# Power_output.net
KiCad netlist of a schematic drawn in Altium Designer
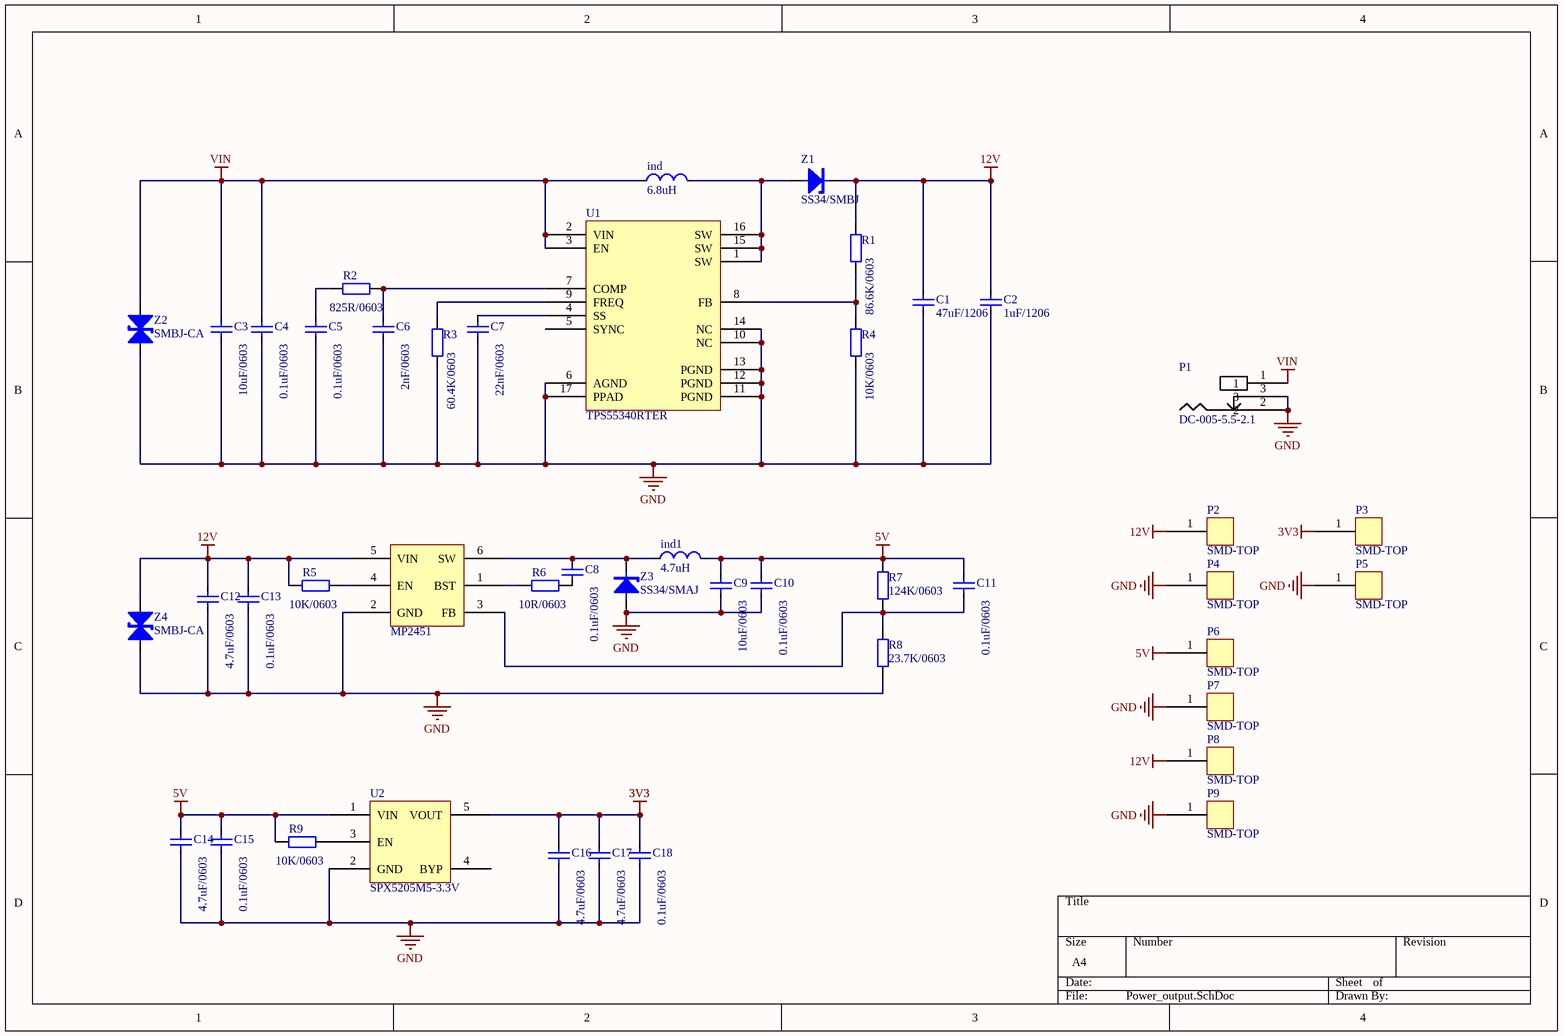
[diagram p0: Power_output.SchDoc]

(export (version "E")
  (design (tool "Eeschema 10.0.6"))
  (components
    (comp (ref "C1")
      (value "47uF/1206")
      (footprint "CAP_1206")
      (description "Capacitor")
      (fields (field (name "Comment") "?uF"))
      (libsource (lib "SchLibrary ") (part "Cap_1206"))
    )
    (comp (ref "C2")
      (value "1uF/1206")
      (footprint "CAP_1206")
      (description "Capacitor")
      (fields (field (name "Comment") "?uF"))
      (libsource (lib "SchLibrary ") (part "Cap_1206"))
    )
    (comp (ref "C3")
      (value "10uF/0603")
      (footprint "CAP_0603")
      (description "Capacitor")
      (fields (field (name "Comment") "?uF"))
      (libsource (lib "SchLibrary ") (part "Cap_0603"))
    )
    (comp (ref "C4")
      (value "0.1uF/0603")
      (footprint "CAP_0603")
      (description "Capacitor")
      (fields (field (name "Comment") "?uF"))
      (libsource (lib "SchLibrary ") (part "Cap_0603"))
    )
    (comp (ref "C5")
      (value "0.1uF/0603")
      (footprint "CAP_0603")
      (description "Capacitor")
      (fields (field (name "Comment") "?uF"))
      (libsource (lib "SchLibrary ") (part "Cap_0603"))
    )
    (comp (ref "C6")
      (value "2nF/0603")
      (footprint "CAP_0603")
      (description "Capacitor")
      (fields (field (name "Comment") "?uF"))
      (libsource (lib "SchLibrary ") (part "Cap_0603"))
    )
    (comp (ref "C7")
      (value "22nF/0603")
      (footprint "CAP_0603")
      (description "Capacitor")
      (fields (field (name "Comment") "?uF"))
      (libsource (lib "SchLibrary ") (part "Cap_0603"))
    )
    (comp (ref "C8")
      (value "0.1uF/0603")
      (footprint "CAP_0603")
      (description "Capacitor")
      (fields (field (name "Comment") "?uF"))
      (libsource (lib "SchLibrary ") (part "Cap_0603"))
    )
    (comp (ref "C9")
      (value "10uF/0603")
      (footprint "CAP_0603")
      (description "Capacitor")
      (fields (field (name "Comment") "?uF"))
      (libsource (lib "SchLibrary ") (part "Cap_0603"))
    )
    (comp (ref "C10")
      (value "0.1uF/0603")
      (footprint "CAP_0603")
      (description "Capacitor")
      (fields (field (name "Comment") "?uF"))
      (libsource (lib "SchLibrary ") (part "Cap_0603"))
    )
    (comp (ref "C11")
      (value "0.1uF/0603")
      (footprint "CAP_0603")
      (description "Capacitor")
      (fields (field (name "Comment") "?uF"))
      (libsource (lib "SchLibrary ") (part "Cap_0603"))
    )
    (comp (ref "C12")
      (value "4.7uF/0603")
      (footprint "CAP_0603")
      (description "Capacitor")
      (fields (field (name "Comment") "?uF"))
      (libsource (lib "SchLibrary ") (part "Cap_0603"))
    )
    (comp (ref "C13")
      (value "0.1uF/0603")
      (footprint "CAP_0603")
      (description "Capacitor")
      (fields (field (name "Comment") "?uF"))
      (libsource (lib "SchLibrary ") (part "Cap_0603"))
    )
    (comp (ref "C14")
      (value "4.7uF/0603")
      (footprint "CAP_0603")
      (description "Capacitor")
      (fields (field (name "Comment") "?uF"))
      (libsource (lib "SchLibrary ") (part "Cap_0603"))
    )
    (comp (ref "C15")
      (value "0.1uF/0603")
      (footprint "CAP_0603")
      (description "Capacitor")
      (fields (field (name "Comment") "?uF"))
      (libsource (lib "SchLibrary ") (part "Cap_0603"))
    )
    (comp (ref "C16")
      (value "4.7uF/0603")
      (footprint "CAP_0603")
      (description "Capacitor")
      (fields (field (name "Comment") "?uF"))
      (libsource (lib "SchLibrary ") (part "Cap_0603"))
    )
    (comp (ref "C17")
      (value "4.7uF/0603")
      (footprint "CAP_0603")
      (description "Capacitor")
      (fields (field (name "Comment") "?uF"))
      (libsource (lib "SchLibrary ") (part "Cap_0603"))
    )
    (comp (ref "C18")
      (value "0.1uF/0603")
      (footprint "CAP_0603")
      (description "Capacitor")
      (fields (field (name "Comment") "?uF"))
      (libsource (lib "SchLibrary ") (part "Cap_0603"))
    )
    (comp (ref "ind") (value "6.8uH") (footprint "IND4*4*2") (libsource (lib "SchLibrary ") (part "Ind")))
    (comp (ref "ind1") (value "4.7uH") (footprint "IND4*4*2") (libsource (lib "SchLibrary ") (part "Ind")))
    (comp (ref "MP2451")
      (value "MP2451")
      (footprint "SOT23-6")
      (description "降压转换器")
      (libsource (lib "SchLibrary ") (part "MP2451"))
    )
    (comp (ref "P1")
      (value "DC-005-5.5-2.1")
      (footprint "DC-005")
      (libsource (lib "SchLibrary ") (part "DC-005-5.5-2.1"))
    )
    (comp (ref "P2") (value "SMD-TOP") (footprint "SMD-TOP") (libsource (lib "SchLibrary ") (part "SMD-TOP")))
    (comp (ref "P3") (value "SMD-TOP") (footprint "SMD-TOP") (libsource (lib "SchLibrary ") (part "SMD-TOP")))
    (comp (ref "P4") (value "SMD-TOP") (footprint "SMD-TOP") (libsource (lib "SchLibrary ") (part "SMD-TOP")))
    (comp (ref "P5") (value "SMD-TOP") (footprint "SMD-TOP") (libsource (lib "SchLibrary ") (part "SMD-TOP")))
    (comp (ref "P6") (value "SMD-TOP") (footprint "SMD-TOP") (libsource (lib "SchLibrary ") (part "SMD-TOP")))
    (comp (ref "P7") (value "SMD-TOP") (footprint "SMD-TOP") (libsource (lib "SchLibrary ") (part "SMD-TOP")))
    (comp (ref "P8") (value "SMD-TOP") (footprint "SMD-TOP") (libsource (lib "SchLibrary ") (part "SMD-TOP")))
    (comp (ref "P9") (value "SMD-TOP") (footprint "SMD-TOP") (libsource (lib "SchLibrary ") (part "SMD-TOP")))
    (comp (ref "R1")
      (value "86.6K/0603")
      (footprint "RES_0603")
      (description "Resistor")
      (fields (field (name "Comment") "?K"))
      (libsource (lib "SchLibrary ") (part "Res_0603"))
    )
    (comp (ref "R2")
      (value "825R/0603")
      (footprint "RES_0603")
      (description "Resistor")
      (fields (field (name "Comment") "?K"))
      (libsource (lib "") (part "Res_0603_1"))
    )
    (comp (ref "R3")
      (value "60.4K/0603")
      (footprint "RES_0603")
      (description "Resistor")
      (fields (field (name "Comment") "?K"))
      (libsource (lib "SchLibrary ") (part "Res_0603"))
    )
    (comp (ref "R4")
      (value "10K/0603")
      (footprint "RES_0603")
      (description "Resistor")
      (fields (field (name "Comment") "?K"))
      (libsource (lib "SchLibrary ") (part "Res_0603"))
    )
    (comp (ref "R5")
      (value "10K/0603")
      (footprint "RES_0603")
      (description "Resistor")
      (fields (field (name "Comment") "?K"))
      (libsource (lib "") (part "Res_0603_1"))
    )
    (comp (ref "R6")
      (value "10R/0603")
      (footprint "RES_0603")
      (description "Resistor")
      (fields (field (name "Comment") "?K"))
      (libsource (lib "") (part "Res_0603_1"))
    )
    (comp (ref "R7")
      (value "124K/0603")
      (footprint "RES_0603")
      (description "Resistor")
      (fields (field (name "Comment") "?K"))
      (libsource (lib "SchLibrary ") (part "Res_0603"))
    )
    (comp (ref "R8")
      (value "23.7K/0603")
      (footprint "RES_0603")
      (description "Resistor")
      (fields (field (name "Comment") "?K"))
      (libsource (lib "SchLibrary ") (part "Res_0603"))
    )
    (comp (ref "R9")
      (value "10K/0603")
      (footprint "RES_0603")
      (description "Resistor")
      (fields (field (name "Comment") "?K"))
      (libsource (lib "") (part "Res_0603_1"))
    )
    (comp (ref "U1")
      (value "TPS55340RTER")
      (footprint "WQFN16")
      (libsource (lib "SchLibrary ") (part "TPS55340RTER"))
    )
    (comp (ref "U2")
      (value "SPX5205M5-3.3V")
      (footprint "SOT23-5")
      (description "LDO IC")
      (libsource (lib "SchLibrary ") (part "SPX5205M5-3.3V"))
    )
    (comp (ref "Z1")
      (value "SS34/SMBJ")
      (footprint "SMB")
      (description "TVS")
      (libsource (lib "SchLibrary ") (part "SMBJ"))
    )
    (comp (ref "Z2")
      (value "SMBJ-CA")
      (footprint "SMB( No proporcionado)")
      (description "TVS")
      (libsource (lib "SchLibrary ") (part "SMBJ-CA"))
    )
    (comp (ref "Z3")
      (value "SS34/SMAJ")
      (footprint "SMA")
      (description "TVS")
      (libsource (lib "SchLibrary ") (part "SMAJ"))
    )
    (comp (ref "Z4")
      (value "SMBJ-CA")
      (footprint "SMB( No proporcionado)")
      (description "TVS")
      (libsource (lib "SchLibrary ") (part "SMBJ-CA"))
    )
  )
  (nets
    (net (code "1") (name "3V3") (class "Default")
      (node (ref "C16") (pin "2") (pinfunction "2_2") (pintype "passive"))
      (node (ref "C17") (pin "2") (pinfunction "2_2") (pintype "passive"))
      (node (ref "C18") (pin "2") (pinfunction "2_2") (pintype "passive"))
      (node (ref "P3") (pin "1") (pinfunction "1_1") (pintype "passive"))
      (node (ref "U2") (pin "5") (pinfunction "VOUT_5") (pintype "passive"))
    )
    (net (code "2") (name "5V") (class "Default")
      (node (ref "C10") (pin "2") (pinfunction "2_2") (pintype "passive"))
      (node (ref "C11") (pin "2") (pinfunction "2_2") (pintype "passive"))
      (node (ref "C14") (pin "2") (pinfunction "2_2") (pintype "passive"))
      (node (ref "C15") (pin "2") (pinfunction "2_2") (pintype "passive"))
      (node (ref "C9") (pin "2") (pinfunction "2_2") (pintype "passive"))
      (node (ref "P6") (pin "1") (pinfunction "1_1") (pintype "passive"))
      (node (ref "R7") (pin "2") (pinfunction "2_2") (pintype "passive"))
      (node (ref "R9") (pin "1") (pinfunction "1_1") (pintype "passive"))
      (node (ref "U2") (pin "1") (pinfunction "VIN_1") (pintype "passive"))
      (node (ref "ind1") (pin "2") (pinfunction "2_2") (pintype "passive"))
    )
    (net (code "3") (name "12V") (class "Default")
      (node (ref "C1") (pin "2") (pinfunction "2_2") (pintype "passive"))
      (node (ref "C12") (pin "2") (pinfunction "2_2") (pintype "passive"))
      (node (ref "C13") (pin "2") (pinfunction "2_2") (pintype "passive"))
      (node (ref "C2") (pin "2") (pinfunction "2_2") (pintype "passive"))
      (node (ref "MP2451") (pin "5") (pinfunction "VIN_5") (pintype "passive"))
      (node (ref "P2") (pin "1") (pinfunction "1_1") (pintype "passive"))
      (node (ref "P8") (pin "1") (pinfunction "1_1") (pintype "passive"))
      (node (ref "R1") (pin "2") (pinfunction "2_2") (pintype "passive"))
      (node (ref "R5") (pin "1") (pinfunction "1_1") (pintype "passive"))
      (node (ref "Z1") (pin "2") (pinfunction "C_2") (pintype "passive"))
      (node (ref "Z4") (pin "2") (pinfunction "C_2") (pintype "passive"))
    )
    (net (code "4") (name "GND") (class "Default")
      (node (ref "C1") (pin "1") (pinfunction "1_1") (pintype "passive"))
      (node (ref "C10") (pin "1") (pinfunction "1_1") (pintype "passive"))
      (node (ref "C12") (pin "1") (pinfunction "1_1") (pintype "passive"))
      (node (ref "C13") (pin "1") (pinfunction "1_1") (pintype "passive"))
      (node (ref "C14") (pin "1") (pinfunction "1_1") (pintype "passive"))
      (node (ref "C15") (pin "1") (pinfunction "1_1") (pintype "passive"))
      (node (ref "C16") (pin "1") (pinfunction "1_1") (pintype "passive"))
      (node (ref "C17") (pin "1") (pinfunction "1_1") (pintype "passive"))
      (node (ref "C18") (pin "1") (pinfunction "1_1") (pintype "passive"))
      (node (ref "C2") (pin "1") (pinfunction "1_1") (pintype "passive"))
      (node (ref "C3") (pin "1") (pinfunction "1_1") (pintype "passive"))
      (node (ref "C4") (pin "1") (pinfunction "1_1") (pintype "passive"))
      (node (ref "C5") (pin "1") (pinfunction "1_1") (pintype "passive"))
      (node (ref "C6") (pin "1") (pinfunction "1_1") (pintype "passive"))
      (node (ref "C7") (pin "1") (pinfunction "1_1") (pintype "passive"))
      (node (ref "C9") (pin "1") (pinfunction "1_1") (pintype "passive"))
      (node (ref "MP2451") (pin "2") (pinfunction "GND_2") (pintype "passive"))
      (node (ref "P1") (pin "2") (pinfunction "2_2") (pintype "passive"))
      (node (ref "P1") (pin "3") (pinfunction "3_3") (pintype "passive"))
      (node (ref "P4") (pin "1") (pinfunction "1_1") (pintype "passive"))
      (node (ref "P5") (pin "1") (pinfunction "1_1") (pintype "passive"))
      (node (ref "P7") (pin "1") (pinfunction "1_1") (pintype "passive"))
      (node (ref "P9") (pin "1") (pinfunction "1_1") (pintype "passive"))
      (node (ref "R3") (pin "1") (pinfunction "1_1") (pintype "passive"))
      (node (ref "R4") (pin "1") (pinfunction "1_1") (pintype "passive"))
      (node (ref "R8") (pin "1") (pinfunction "1_1") (pintype "passive"))
      (node (ref "U1") (pin "10") (pinfunction "NC_10") (pintype "passive"))
      (node (ref "U1") (pin "11") (pinfunction "PGND_11") (pintype "passive"))
      (node (ref "U1") (pin "12") (pinfunction "PGND_12") (pintype "passive"))
      (node (ref "U1") (pin "13") (pinfunction "PGND_13") (pintype "passive"))
      (node (ref "U1") (pin "14") (pinfunction "NC_14") (pintype "passive"))
      (node (ref "U1") (pin "17") (pinfunction "PPAD_17") (pintype "passive"))
      (node (ref "U1") (pin "6") (pinfunction "AGND_6") (pintype "passive"))
      (node (ref "U2") (pin "2") (pinfunction "GND_2") (pintype "passive"))
      (node (ref "Z2") (pin "1") (pinfunction "A_1") (pintype "passive"))
      (node (ref "Z3") (pin "1") (pinfunction "A_1") (pintype "passive"))
      (node (ref "Z4") (pin "1") (pinfunction "A_1") (pintype "passive"))
    )
    (net (code "5") (name "Net-(C5-Pad2)") (class "Default")
      (node (ref "C5") (pin "2") (pinfunction "2_2") (pintype "passive"))
      (node (ref "R2") (pin "1") (pinfunction "1_1") (pintype "passive"))
    )
    (net (code "6") (name "Net-(C8-Pad1)") (class "Default")
      (node (ref "C8") (pin "1") (pinfunction "1_1") (pintype "passive"))
      (node (ref "R6") (pin "2") (pinfunction "2_2") (pintype "passive"))
    )
    (net (code "7") (name "Net-(MP2451-BST)") (class "Default")
      (node (ref "MP2451") (pin "1") (pinfunction "BST_1") (pintype "passive"))
      (node (ref "R6") (pin "1") (pinfunction "1_1") (pintype "passive"))
    )
    (net (code "8") (name "Net-(MP2451-EN)") (class "Default")
      (node (ref "MP2451") (pin "4") (pinfunction "EN_4") (pintype "passive"))
      (node (ref "R5") (pin "2") (pinfunction "2_2") (pintype "passive"))
    )
    (net (code "9") (name "Net-(MP2451-FB)") (class "Default")
      (node (ref "C11") (pin "1") (pinfunction "1_1") (pintype "passive"))
      (node (ref "MP2451") (pin "3") (pinfunction "FB_3") (pintype "passive"))
      (node (ref "R7") (pin "1") (pinfunction "1_1") (pintype "passive"))
      (node (ref "R8") (pin "2") (pinfunction "2_2") (pintype "passive"))
    )
    (net (code "10") (name "Net-(MP2451-SW)") (class "Default")
      (node (ref "C8") (pin "2") (pinfunction "2_2") (pintype "passive"))
      (node (ref "MP2451") (pin "6") (pinfunction "SW_6") (pintype "passive"))
      (node (ref "Z3") (pin "2") (pinfunction "C_2") (pintype "passive"))
      (node (ref "ind1") (pin "1") (pinfunction "1_1") (pintype "passive"))
    )
    (net (code "11") (name "Net-(U1-COMP)") (class "Default")
      (node (ref "C6") (pin "2") (pinfunction "2_2") (pintype "passive"))
      (node (ref "R2") (pin "2") (pinfunction "2_2") (pintype "passive"))
      (node (ref "U1") (pin "7") (pinfunction "COMP_7") (pintype "passive"))
    )
    (net (code "12") (name "Net-(U1-FB)") (class "Default")
      (node (ref "R1") (pin "1") (pinfunction "1_1") (pintype "passive"))
      (node (ref "R4") (pin "2") (pinfunction "2_2") (pintype "passive"))
      (node (ref "U1") (pin "8") (pinfunction "FB_8") (pintype "passive"))
    )
    (net (code "13") (name "Net-(U1-FREQ)") (class "Default")
      (node (ref "R3") (pin "2") (pinfunction "2_2") (pintype "passive"))
      (node (ref "U1") (pin "9") (pinfunction "FREQ_9") (pintype "passive"))
    )
    (net (code "14") (name "Net-(U1-SS)") (class "Default")
      (node (ref "C7") (pin "2") (pinfunction "2_2") (pintype "passive"))
      (node (ref "U1") (pin "4") (pinfunction "SS_4") (pintype "passive"))
    )
    (net (code "15") (name "Net-(U2-EN)") (class "Default")
      (node (ref "R9") (pin "2") (pinfunction "2_2") (pintype "passive"))
      (node (ref "U2") (pin "3") (pinfunction "EN_3") (pintype "passive"))
    )
    (net (code "16") (name "Net-(Z1-A)") (class "Default")
      (node (ref "U1") (pin "1") (pinfunction "SW_1") (pintype "passive"))
      (node (ref "U1") (pin "15") (pinfunction "SW_15") (pintype "passive"))
      (node (ref "U1") (pin "16") (pinfunction "SW_16") (pintype "passive"))
      (node (ref "Z1") (pin "1") (pinfunction "A_1") (pintype "passive"))
      (node (ref "ind") (pin "2") (pinfunction "2_2") (pintype "passive"))
    )
    (net (code "17") (name "VIN") (class "Default")
      (node (ref "C3") (pin "2") (pinfunction "2_2") (pintype "passive"))
      (node (ref "C4") (pin "2") (pinfunction "2_2") (pintype "passive"))
      (node (ref "P1") (pin "1") (pinfunction "1_1") (pintype "passive"))
      (node (ref "U1") (pin "2") (pinfunction "VIN_2") (pintype "passive"))
      (node (ref "U1") (pin "3") (pinfunction "EN_3") (pintype "passive"))
      (node (ref "Z2") (pin "2") (pinfunction "C_2") (pintype "passive"))
      (node (ref "ind") (pin "1") (pinfunction "1_1") (pintype "passive"))
    )
    (net (code "18") (name "unconnected-(U1-SYNC-Pad5)") (class "Default")
      (node (ref "U1") (pin "5") (pinfunction "SYNC_5") (pintype "passive"))
    )
    (net (code "19") (name "unconnected-(U2-BYP-Pad4)") (class "Default")
      (node (ref "U2") (pin "4") (pinfunction "BYP_4") (pintype "passive"))
    )
  )
)
